# IMU_Board.net
KiCad netlist of a schematic drawn in EAGLE
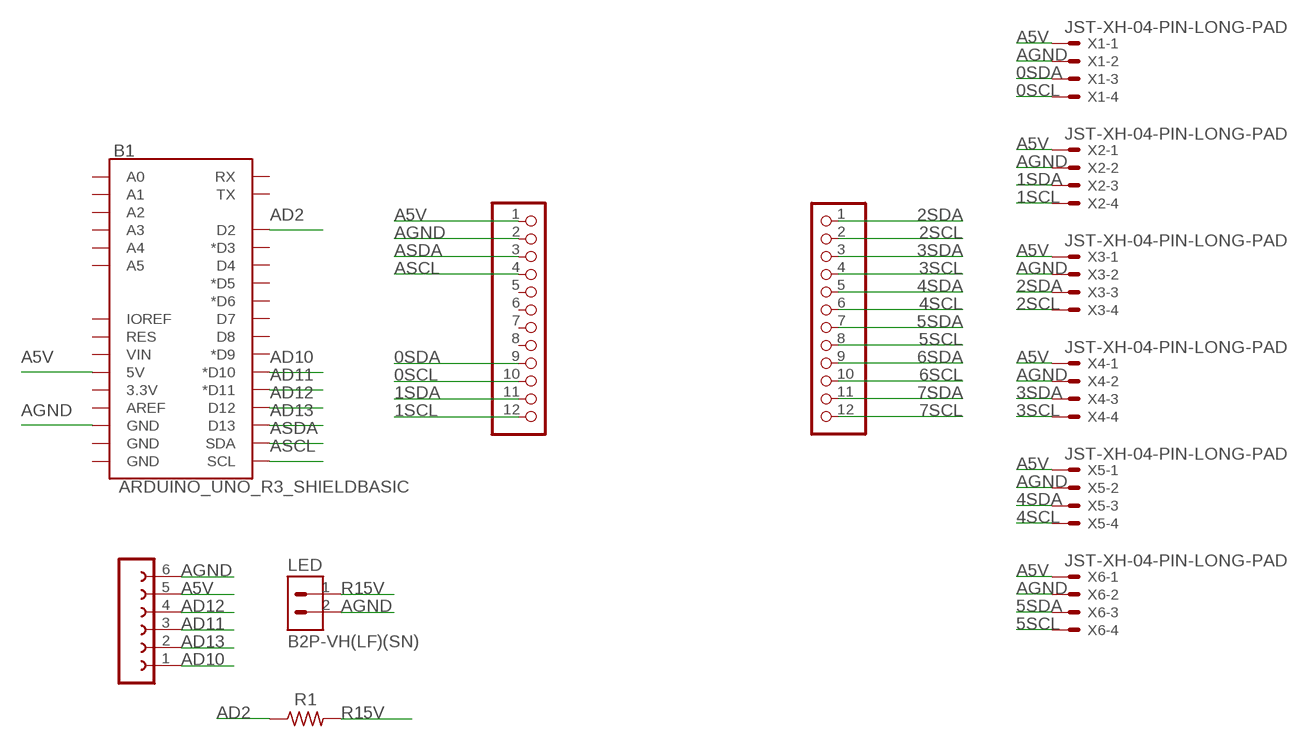
[diagram p0: schematic, sheet 1]

(export (version "E")
  (design (tool "Eeschema 10.0.6"))
  (components
    (comp (ref "B1")
      (value "ARDUINO_UNO_R3_SHIELDBASIC")
      (footprint "eagle-import:UNO_R3_SHIELD")
      (libsource (lib "eagle-import") (part "ARDUINO_UNO_R3_SHIELDBASIC"))
    )
    (comp (ref "JP1")
      (value "HEADER-1X12")
      (footprint "eagle-import:1X12_ROUND")
      (libsource (lib "eagle-import") (part "HEADER-1X12"))
    )
    (comp (ref "JP3")
      (value "HEADER-1X12")
      (footprint "eagle-import:1X12_ROUND")
      (libsource (lib "eagle-import") (part "HEADER-1X12"))
    )
    (comp (ref "LED")
      (value "B2P-VH(LF)(SN)")
      (footprint "eagle-import:HDR-02")
      (fields
        (field (name "DIGIKEY_PART_NUMBER") "455-1639-ND")
        (field (name "MANUFACTURER") "JST Sales America Inc.")
        (field (name "CREATED_BY") "PCBLayout.com")
      )
      (libsource (lib "eagle-import") (part "B2P-VH(LF)(SN)"))
    )
    (comp (ref "R1")
      (value "R-US_AXIAL-11.7MM-PITCH")
      (footprint "eagle-import:RESAD1176W63L850D250B")
      (libsource (lib "eagle-import") (part "R-USAXIAL-11.7MM-PITCH_"))
    )
    (comp (ref "SD")
      (value "FE06-1")
      (footprint "eagle-import:FE06")
      (libsource (lib "eagle-import") (part "FE06-1"))
    )
    (comp (ref "X1")
      (value "JST-XH-04-PIN-LONG-PAD")
      (footprint "eagle-import:JST-XH-04-PACKAGE-LONG-PAD")
      (libsource (lib "eagle-import") (part "JST-XH-04-PIN-LONG-PAD"))
    )
    (comp (ref "X2")
      (value "JST-XH-04-PIN-LONG-PAD")
      (footprint "eagle-import:JST-XH-04-PACKAGE-LONG-PAD")
      (libsource (lib "eagle-import") (part "JST-XH-04-PIN-LONG-PAD"))
    )
    (comp (ref "X3")
      (value "JST-XH-04-PIN-LONG-PAD")
      (footprint "eagle-import:JST-XH-04-PACKAGE-LONG-PAD")
      (libsource (lib "eagle-import") (part "JST-XH-04-PIN-LONG-PAD"))
    )
    (comp (ref "X4")
      (value "JST-XH-04-PIN-LONG-PAD")
      (footprint "eagle-import:JST-XH-04-PACKAGE-LONG-PAD")
      (libsource (lib "eagle-import") (part "JST-XH-04-PIN-LONG-PAD"))
    )
    (comp (ref "X5")
      (value "JST-XH-04-PIN-LONG-PAD")
      (footprint "eagle-import:JST-XH-04-PACKAGE-LONG-PAD")
      (libsource (lib "eagle-import") (part "JST-XH-04-PIN-LONG-PAD"))
    )
    (comp (ref "X6")
      (value "JST-XH-04-PIN-LONG-PAD")
      (footprint "eagle-import:JST-XH-04-PACKAGE-LONG-PAD")
      (libsource (lib "eagle-import") (part "JST-XH-04-PIN-LONG-PAD"))
    )
  )
  (nets
    (net (code "1") (name "/0SCL") (class "Default")
      (node (ref "JP3") (pin "10") (pinfunction "10_10") (pintype "passive"))
      (node (ref "X1") (pin "4") (pinfunction "S_4") (pintype "passive"))
    )
    (net (code "2") (name "/0SDA") (class "Default")
      (node (ref "JP3") (pin "9") (pinfunction "9_9") (pintype "passive"))
      (node (ref "X1") (pin "3") (pinfunction "S_3") (pintype "passive"))
    )
    (net (code "3") (name "/1SCL") (class "Default")
      (node (ref "JP3") (pin "12") (pinfunction "12_12") (pintype "passive"))
      (node (ref "X2") (pin "4") (pinfunction "S_4") (pintype "passive"))
    )
    (net (code "4") (name "/1SDA") (class "Default")
      (node (ref "JP3") (pin "11") (pinfunction "11_11") (pintype "passive"))
      (node (ref "X2") (pin "3") (pinfunction "S_3") (pintype "passive"))
    )
    (net (code "5") (name "/2SCL") (class "Default")
      (node (ref "JP1") (pin "2") (pinfunction "2_2") (pintype "passive"))
      (node (ref "X3") (pin "4") (pinfunction "S_4") (pintype "passive"))
    )
    (net (code "6") (name "/2SDA") (class "Default")
      (node (ref "JP1") (pin "1") (pinfunction "1_1") (pintype "passive"))
      (node (ref "X3") (pin "3") (pinfunction "S_3") (pintype "passive"))
    )
    (net (code "7") (name "/3SCL") (class "Default")
      (node (ref "JP1") (pin "4") (pinfunction "4_4") (pintype "passive"))
      (node (ref "X4") (pin "4") (pinfunction "S_4") (pintype "passive"))
    )
    (net (code "8") (name "/3SDA") (class "Default")
      (node (ref "JP1") (pin "3") (pinfunction "3_3") (pintype "passive"))
      (node (ref "X4") (pin "3") (pinfunction "S_3") (pintype "passive"))
    )
    (net (code "9") (name "/4SCL") (class "Default")
      (node (ref "JP1") (pin "6") (pinfunction "6_6") (pintype "passive"))
      (node (ref "X5") (pin "4") (pinfunction "S_4") (pintype "passive"))
    )
    (net (code "10") (name "/4SDA") (class "Default")
      (node (ref "JP1") (pin "5") (pinfunction "5_5") (pintype "passive"))
      (node (ref "X5") (pin "3") (pinfunction "S_3") (pintype "passive"))
    )
    (net (code "11") (name "/5SCL") (class "Default")
      (node (ref "JP1") (pin "8") (pinfunction "8_8") (pintype "passive"))
      (node (ref "X6") (pin "4") (pinfunction "S_4") (pintype "passive"))
    )
    (net (code "12") (name "/5SDA") (class "Default")
      (node (ref "JP1") (pin "7") (pinfunction "7_7") (pintype "passive"))
      (node (ref "X6") (pin "3") (pinfunction "S_3") (pintype "passive"))
    )
    (net (code "13") (name "/6SCL") (class "Default")
      (node (ref "JP1") (pin "10") (pinfunction "10_10") (pintype "passive"))
    )
    (net (code "14") (name "/6SDA") (class "Default")
      (node (ref "JP1") (pin "9") (pinfunction "9_9") (pintype "passive"))
    )
    (net (code "15") (name "/7SCL") (class "Default")
      (node (ref "JP1") (pin "12") (pinfunction "12_12") (pintype "passive"))
    )
    (net (code "16") (name "/7SDA") (class "Default")
      (node (ref "JP1") (pin "11") (pinfunction "11_11") (pintype "passive"))
    )
    (net (code "17") (name "/A5V") (class "Default")
      (node (ref "B1") (pin "5V") (pinfunction "5V_5V") (pintype "bidirectional"))
      (node (ref "JP3") (pin "1") (pinfunction "1_1") (pintype "passive"))
      (node (ref "SD") (pin "5") (pinfunction "5_5") (pintype "passive"))
      (node (ref "X1") (pin "1") (pinfunction "S_1") (pintype "passive"))
      (node (ref "X2") (pin "1") (pinfunction "S_1") (pintype "passive"))
      (node (ref "X3") (pin "1") (pinfunction "S_1") (pintype "passive"))
      (node (ref "X4") (pin "1") (pinfunction "S_1") (pintype "passive"))
      (node (ref "X5") (pin "1") (pinfunction "S_1") (pintype "passive"))
      (node (ref "X6") (pin "1") (pinfunction "S_1") (pintype "passive"))
    )
    (net (code "18") (name "/AD2") (class "Default")
      (node (ref "B1") (pin "D2") (pinfunction "D2_D2") (pintype "bidirectional"))
      (node (ref "R1") (pin "1") (pinfunction "1_1") (pintype "passive"))
    )
    (net (code "19") (name "/AD10") (class "Default")
      (node (ref "B1") (pin "D10") (pinfunction "*D10_D10") (pintype "bidirectional"))
      (node (ref "SD") (pin "1") (pinfunction "1_1") (pintype "passive"))
    )
    (net (code "20") (name "/AD11") (class "Default")
      (node (ref "B1") (pin "D11") (pinfunction "*D11_D11") (pintype "bidirectional"))
      (node (ref "SD") (pin "3") (pinfunction "3_3") (pintype "passive"))
    )
    (net (code "21") (name "/AD12") (class "Default")
      (node (ref "B1") (pin "D12") (pinfunction "D12_D12") (pintype "bidirectional"))
      (node (ref "SD") (pin "4") (pinfunction "4_4") (pintype "passive"))
    )
    (net (code "22") (name "/AD13") (class "Default")
      (node (ref "B1") (pin "D13") (pinfunction "D13_D13") (pintype "bidirectional"))
      (node (ref "SD") (pin "2") (pinfunction "2_2") (pintype "passive"))
    )
    (net (code "23") (name "/AGND") (class "Default")
      (node (ref "B1") (pin "GND@2") (pinfunction "GND_GND@2") (pintype "bidirectional"))
      (node (ref "JP3") (pin "2") (pinfunction "2_2") (pintype "passive"))
      (node (ref "LED") (pin "2") (pinfunction "2_2") (pintype "passive"))
      (node (ref "SD") (pin "6") (pinfunction "6_6") (pintype "passive"))
      (node (ref "X1") (pin "2") (pinfunction "S_2") (pintype "passive"))
      (node (ref "X2") (pin "2") (pinfunction "S_2") (pintype "passive"))
      (node (ref "X3") (pin "2") (pinfunction "S_2") (pintype "passive"))
      (node (ref "X4") (pin "2") (pinfunction "S_2") (pintype "passive"))
      (node (ref "X5") (pin "2") (pinfunction "S_2") (pintype "passive"))
      (node (ref "X6") (pin "2") (pinfunction "S_2") (pintype "passive"))
    )
    (net (code "24") (name "/ASCL") (class "Default")
      (node (ref "B1") (pin "SCL") (pinfunction "SCL_SCL") (pintype "bidirectional"))
      (node (ref "JP3") (pin "4") (pinfunction "4_4") (pintype "passive"))
    )
    (net (code "25") (name "/ASDA") (class "Default")
      (node (ref "B1") (pin "SDA") (pinfunction "SDA_SDA") (pintype "bidirectional"))
      (node (ref "JP3") (pin "3") (pinfunction "3_3") (pintype "passive"))
    )
    (net (code "26") (name "/R15V") (class "Default")
      (node (ref "LED") (pin "1") (pinfunction "1_1") (pintype "passive"))
      (node (ref "R1") (pin "2") (pinfunction "2_2") (pintype "passive"))
    )
    (net (code "27") (name "unconnected-(B1-*D3-PadD3)") (class "Default")
      (node (ref "B1") (pin "D3") (pinfunction "*D3_D3") (pintype "bidirectional"))
    )
    (net (code "28") (name "unconnected-(B1-*D5-PadD5)") (class "Default")
      (node (ref "B1") (pin "D5") (pinfunction "*D5_D5") (pintype "bidirectional"))
    )
    (net (code "29") (name "unconnected-(B1-*D6-PadD6)") (class "Default")
      (node (ref "B1") (pin "D6") (pinfunction "*D6_D6") (pintype "bidirectional"))
    )
    (net (code "30") (name "unconnected-(B1-*D9-PadD9)") (class "Default")
      (node (ref "B1") (pin "D9") (pinfunction "*D9_D9") (pintype "bidirectional"))
    )
    (net (code "31") (name "unconnected-(B1-GND-PadGND@0)") (class "Default")
      (node (ref "B1") (pin "GND@0") (pinfunction "GND_GND@0") (pintype "bidirectional"))
    )
    (net (code "32") (name "unconnected-(B1-GND-PadGND@1)") (class "Default")
      (node (ref "B1") (pin "GND@1") (pinfunction "GND_GND@1") (pintype "bidirectional"))
    )
    (net (code "33") (name "unconnected-(B1-Pad3.3V)") (class "Default")
      (node (ref "B1") (pin "3.3V") (pinfunction "3.3V_3.3V") (pintype "bidirectional"))
    )
    (net (code "34") (name "unconnected-(B1-PadA0)") (class "Default")
      (node (ref "B1") (pin "A0") (pinfunction "A0_A0") (pintype "bidirectional"))
    )
    (net (code "35") (name "unconnected-(B1-PadA1)") (class "Default")
      (node (ref "B1") (pin "A1") (pinfunction "A1_A1") (pintype "bidirectional"))
    )
    (net (code "36") (name "unconnected-(B1-PadA2)") (class "Default")
      (node (ref "B1") (pin "A2") (pinfunction "A2_A2") (pintype "bidirectional"))
    )
    (net (code "37") (name "unconnected-(B1-PadA3)") (class "Default")
      (node (ref "B1") (pin "A3") (pinfunction "A3_A3") (pintype "bidirectional"))
    )
    (net (code "38") (name "unconnected-(B1-PadA4)") (class "Default")
      (node (ref "B1") (pin "A4") (pinfunction "A4_A4") (pintype "bidirectional"))
    )
    (net (code "39") (name "unconnected-(B1-PadA5)") (class "Default")
      (node (ref "B1") (pin "A5") (pinfunction "A5_A5") (pintype "bidirectional"))
    )
    (net (code "40") (name "unconnected-(B1-PadAREF)") (class "Default")
      (node (ref "B1") (pin "AREF") (pinfunction "AREF_AREF") (pintype "bidirectional"))
    )
    (net (code "41") (name "unconnected-(B1-PadD4)") (class "Default")
      (node (ref "B1") (pin "D4") (pinfunction "D4_D4") (pintype "bidirectional"))
    )
    (net (code "42") (name "unconnected-(B1-PadD7)") (class "Default")
      (node (ref "B1") (pin "D7") (pinfunction "D7_D7") (pintype "bidirectional"))
    )
    (net (code "43") (name "unconnected-(B1-PadD8)") (class "Default")
      (node (ref "B1") (pin "D8") (pinfunction "D8_D8") (pintype "bidirectional"))
    )
    (net (code "44") (name "unconnected-(B1-PadIOREF)") (class "Default")
      (node (ref "B1") (pin "IOREF") (pinfunction "IOREF_IOREF") (pintype "bidirectional"))
    )
    (net (code "45") (name "unconnected-(B1-PadRES)") (class "Default")
      (node (ref "B1") (pin "RES") (pinfunction "RES_RES") (pintype "bidirectional"))
    )
    (net (code "46") (name "unconnected-(B1-PadRX)") (class "Default")
      (node (ref "B1") (pin "RX") (pinfunction "RX_RX") (pintype "bidirectional"))
    )
    (net (code "47") (name "unconnected-(B1-PadTX)") (class "Default")
      (node (ref "B1") (pin "TX") (pinfunction "TX_TX") (pintype "bidirectional"))
    )
    (net (code "48") (name "unconnected-(B1-PadVIN)") (class "Default")
      (node (ref "B1") (pin "VIN") (pinfunction "VIN_VIN") (pintype "bidirectional"))
    )
    (net (code "49") (name "unconnected-(JP3-Pad5)") (class "Default")
      (node (ref "JP3") (pin "5") (pinfunction "5_5") (pintype "passive"))
    )
    (net (code "50") (name "unconnected-(JP3-Pad6)") (class "Default")
      (node (ref "JP3") (pin "6") (pinfunction "6_6") (pintype "passive"))
    )
    (net (code "51") (name "unconnected-(JP3-Pad7)") (class "Default")
      (node (ref "JP3") (pin "7") (pinfunction "7_7") (pintype "passive"))
    )
    (net (code "52") (name "unconnected-(JP3-Pad8)") (class "Default")
      (node (ref "JP3") (pin "8") (pinfunction "8_8") (pintype "passive"))
    )
  )
)
